# 15_2ND_AP1302_ISP.net
KiCad netlist of a schematic drawn in Altium Designer
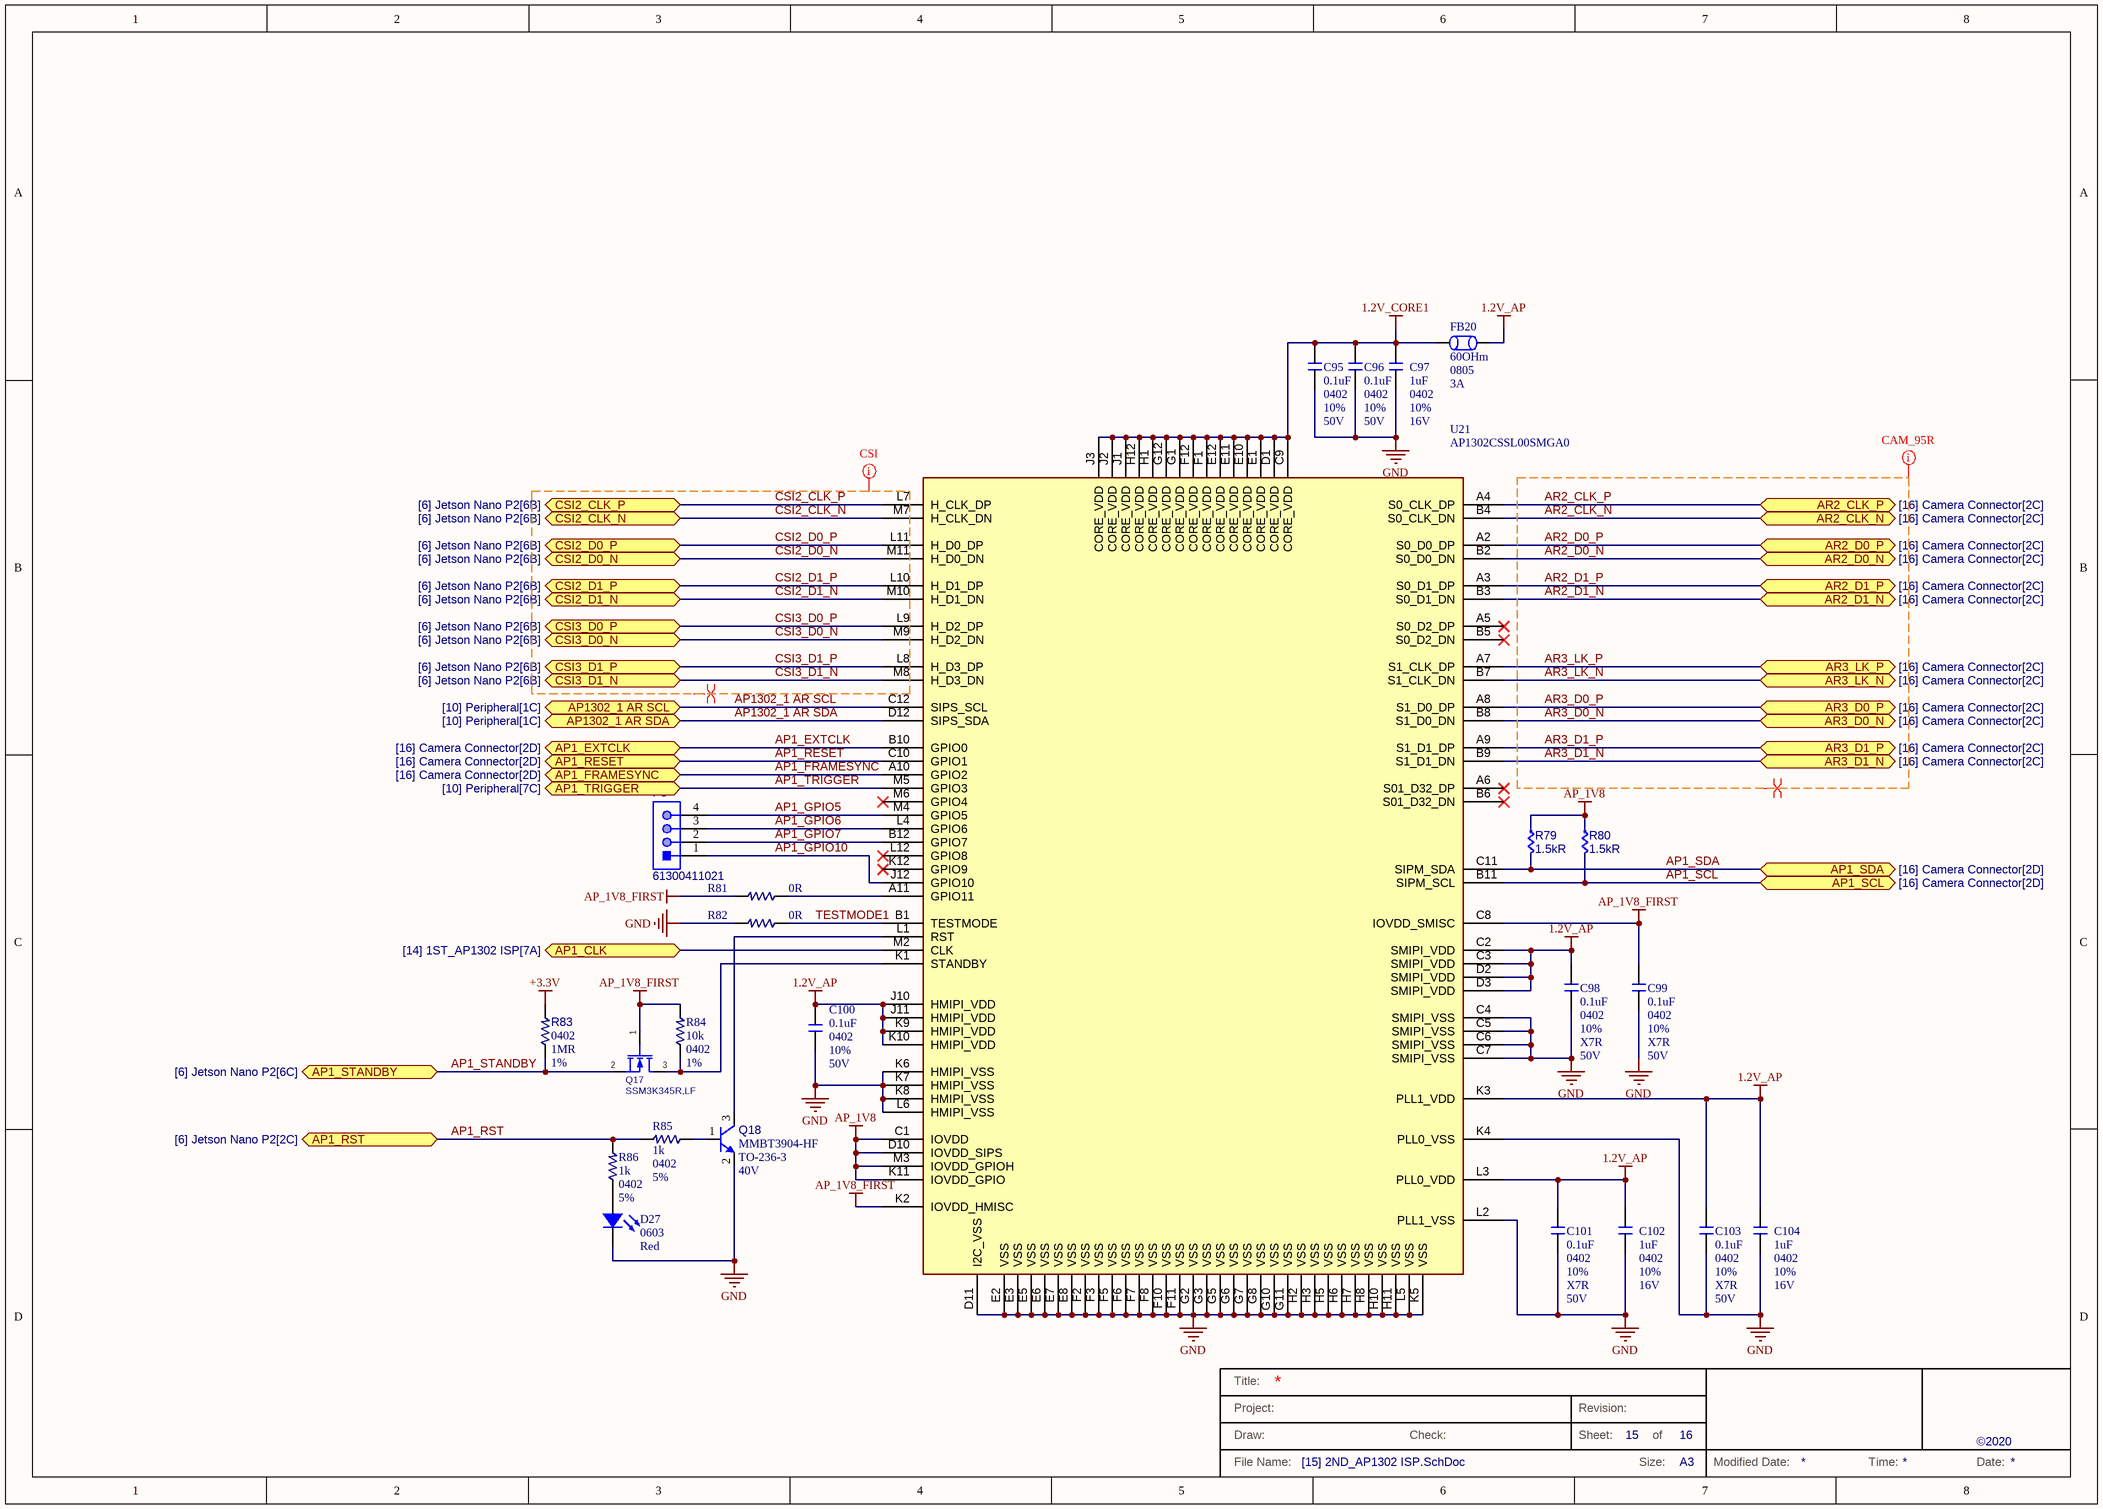
[diagram p0: [15] 2ND_AP1302 ISP.SchDoc]

(export (version "E")
  (design (tool "Eeschema 10.0.6"))
  (components
    (comp (ref "C95")
      (value "0.1uF")
      (footprint "C0402M")
      (description "CAP CER 0.1UF 50V X7R 0402")
      (fields
        (field (name "MANUFACTURER") "Murata")
        (field (name "MANUFACTURER PART NUMBER") "GRM155R71H104KE14D")
        (field (name "CASE/PACKAGE") "0402")
        (field (name "TOLERANCE") "10%")
        (field (name "VOLTAGE") "50V")
      )
      (libsource (lib "") (part "CAP_CER_1"))
    )
    (comp (ref "C96")
      (value "0.1uF")
      (footprint "C0402M")
      (description "CAP CER 0.1UF 50V X7R 0402")
      (fields
        (field (name "MANUFACTURER") "Murata")
        (field (name "MANUFACTURER PART NUMBER") "GRM155R71H104KE14D")
        (field (name "CASE/PACKAGE") "0402")
        (field (name "TOLERANCE") "10%")
        (field (name "VOLTAGE") "50V")
      )
      (libsource (lib "") (part "CAP_CER_1"))
    )
    (comp (ref "C97")
      (value "1uF")
      (footprint "C0402M")
      (fields
        (field (name "CASE CODE (IMPERIAL)") "0402")
        (field (name "TOLERANCE") "10%")
        (field (name "VOLTAGE") "16V")
      )
      (libsource (lib "CommonLib") (part "CAP_CER"))
    )
    (comp (ref "C98")
      (value "0.1uF")
      (footprint "C0402M")
      (description "CAP CER 0.1UF 50V X7R 0402")
      (fields
        (field (name "MANUFACTURER") "Murata")
        (field (name "MANUFACTURER PART NUMBER") "GRM155R71H104KE14D")
        (field (name "CASE/PACKAGE") "0402")
        (field (name "TOLERANCE") "10%")
        (field (name "DIELECTRIC") "X7R")
        (field (name "VOLTAGE") "50V")
      )
      (libsource (lib "") (part "CAP_CER_1"))
    )
    (comp (ref "C99")
      (value "0.1uF")
      (footprint "C0402M")
      (description "CAP CER 0.1UF 50V X7R 0402")
      (fields
        (field (name "MANUFACTURER") "Murata")
        (field (name "MANUFACTURER PART NUMBER") "GRM155R71H104KE14D")
        (field (name "CASE/PACKAGE") "0402")
        (field (name "TOLERANCE") "10%")
        (field (name "DIELECTRIC") "X7R")
        (field (name "VOLTAGE") "50V")
      )
      (libsource (lib "") (part "CAP_CER_1"))
    )
    (comp (ref "C100")
      (value "0.1uF")
      (footprint "C0402M")
      (description "CAP CER 0.1UF 50V X7R 0402")
      (fields
        (field (name "MANUFACTURER") "Murata")
        (field (name "MANUFACTURER PART NUMBER") "GRM155R71H104KE14D")
        (field (name "CASE/PACKAGE") "0402")
        (field (name "TOLERANCE") "10%")
        (field (name "VOLTAGE") "50V")
      )
      (libsource (lib "") (part "CAP_CER_1"))
    )
    (comp (ref "C101")
      (value "0.1uF")
      (footprint "C0402M")
      (description "CAP CER 0.1UF 50V X7R 0402")
      (fields
        (field (name "MANUFACTURER") "Murata")
        (field (name "MANUFACTURER PART NUMBER") "GRM155R71H104KE14D")
        (field (name "CASE/PACKAGE") "0402")
        (field (name "TOLERANCE") "10%")
        (field (name "DIELECTRIC") "X7R")
        (field (name "VOLTAGE") "50V")
      )
      (libsource (lib "") (part "CAP_CER_1"))
    )
    (comp (ref "C102")
      (value "1uF")
      (footprint "C0402M")
      (fields
        (field (name "CASE CODE (IMPERIAL)") "0402")
        (field (name "TOLERANCE") "10%")
        (field (name "VOLTAGE") "16V")
      )
      (libsource (lib "CommonLib") (part "CAP_CER"))
    )
    (comp (ref "C103")
      (value "0.1uF")
      (footprint "C0402M")
      (description "CAP CER 0.1UF 50V X7R 0402")
      (fields
        (field (name "MANUFACTURER") "Murata")
        (field (name "MANUFACTURER PART NUMBER") "GRM155R71H104KE14D")
        (field (name "CASE/PACKAGE") "0402")
        (field (name "TOLERANCE") "10%")
        (field (name "DIELECTRIC") "X7R")
        (field (name "VOLTAGE") "50V")
      )
      (libsource (lib "") (part "CAP_CER_1"))
    )
    (comp (ref "C104")
      (value "1uF")
      (footprint "C0402M")
      (fields
        (field (name "CASE CODE (IMPERIAL)") "0402")
        (field (name "TOLERANCE") "10%")
        (field (name "VOLTAGE") "16V")
      )
      (libsource (lib "CommonLib") (part "CAP_CER"))
    )
    (comp (ref "D27")
      (value "LTST-C190CKT")
      (footprint "LED-0603")
      (description "LED RED CLEAR CHIP SMD")
      (fields (field (name "CASE/PACKAGE") "0603") (field (name "COLOR") "Red"))
      (libsource (lib "CommonLib") (part "Led"))
    )
    (comp (ref "FB20")
      (value "60OHm")
      (footprint "R0805M")
      (fields
        (field (name "CASE CODE (IMPERIAL)") "0805")
        (field (name "TOLERANCE") "25%")
        (field (name "MAX DC CURRENT") "3A")
      )
      (libsource (lib "CommonLib") (part "FB"))
    )
    (comp (ref "P8")
      (value "61300411021")
      (footprint "61300411021")
      (description "CONN HEADER R/A 4POS 2.54MM")
      (fields (field (name "MANUFACTURER") "Würth Elektronik GmbH"))
      (libsource (lib "3DAS_4Camera") (part "WE-CN-1P-M-R4"))
    )
    (comp (ref "Q17")
      (value "SSM3K345R,LF")
      (footprint "SSM3K345R,LF-Footprint-1")
      (description "MOSFET N-CHANNEL 20V 4A SOT23F")
      (libsource (lib "Altium Central") (part "SSM3K345R,LF"))
    )
    (comp (ref "Q18")
      (value "NPN")
      (footprint "SOT55P160X90-3N")
      (description "TRANS NPN 40V 0.2A SOT523")
      (fields
        (field (name "MANUFACTURER PART NUMBER 1") "MMBT3904-HF")
        (field (name "CASE/PACKAGE") "TO-236-3")
        (field (name "COLLECTOR EMITTER BREAKDOWN VOLTAGE") "40V")
      )
      (libsource (lib "3DAS_4Camera") (part "NPN"))
    )
    (comp (ref "R79")
      (value "ERJ-2RKF1501X")
      (footprint "RES0402")
      (description "RES SMD 1.5K OHM 1% 1/10W 0402")
      (fields (field (name "RESISTANCE") "1.5kR") (field (name "TOLERANCE") "1%"))
      (libsource (lib "Altium Central") (part "=Resistance"))
    )
    (comp (ref "R80")
      (value "ERJ-2RKF1501X")
      (footprint "RES0402")
      (description "RES SMD 1.5K OHM 1% 1/10W 0402")
      (fields (field (name "RESISTANCE") "1.5kR") (field (name "TOLERANCE") "1%"))
      (libsource (lib "Altium Central") (part "=Resistance"))
    )
    (comp (ref "R81")
      (value "RC0402FR-070RL")
      (footprint "R0402M")
      (description "RC Series 0402 0.063 W 0 Ohm Jumper Surface Mount Thick Film Chip Resistor")
      (fields (field (name "RESISTANCE") "0R") (field (name "TOLERANCE") "1%"))
      (libsource (lib "CommonLib") (part "RES_SMD"))
    )
    (comp (ref "R82")
      (value "RC0402FR-070RL")
      (footprint "R0402M")
      (description "RC Series 0402 0.063 W 0 Ohm Jumper Surface Mount Thick Film Chip Resistor")
      (fields (field (name "RESISTANCE") "0R") (field (name "TOLERANCE") "1%"))
      (libsource (lib "CommonLib") (part "RES_SMD"))
    )
    (comp (ref "R83")
      (value "1M")
      (footprint "R0402M")
      (description "RES SMD 1M OHM 1% 1/16W 0402")
      (fields
        (field (name "MANUFACTURER") "Yageo")
        (field (name "MANUFACTURER PART NUMBER") "RC0402FR-071ML")
        (field (name "CASE CODE (IMPERIAL)") "0402")
        (field (name "RESISTANCE") "1MR")
        (field (name "TOLERANCE") "1%")
      )
      (libsource (lib "3DAS_4Camera") (part "RES_SMD_17"))
    )
    (comp (ref "R84")
      (value "10k")
      (footprint "R0402M")
      (description "RES SMD 10K OHM 1% 1/16W 0402")
      (fields
        (field (name "MANUFACTURER") "Yageo")
        (field (name "MANUFACTURER PART NUMBER") "RC0402FR-0710KL")
        (field (name "CASE CODE (IMPERIAL)") "0402")
        (field (name "TOLERANCE") "1%")
      )
      (libsource (lib "CommonLib") (part "RES_SMD"))
    )
    (comp (ref "R85")
      (value "1k")
      (footprint "R0402M")
      (description "RES SMD 1K OHM 5% 1/16W 0402")
      (fields
        (field (name "MANUFACTURER") "Yageo")
        (field (name "MANUFACTURER PART NUMBER") "RC0402JR-071KL")
        (field (name "CASE CODE (IMPERIAL)") "0402")
        (field (name "TOLERANCE") "5%")
      )
      (libsource (lib "CommonLib") (part "RES_SMD"))
    )
    (comp (ref "R86")
      (value "1k")
      (footprint "R0402M")
      (description "RES SMD 1K OHM 5% 1/16W 0402")
      (fields
        (field (name "MANUFACTURER") "Yageo")
        (field (name "MANUFACTURER PART NUMBER") "RC0402JR-071KL")
        (field (name "CASE CODE (IMPERIAL)") "0402")
        (field (name "TOLERANCE") "5%")
      )
      (libsource (lib "CommonLib") (part "RES_SMD"))
    )
    (comp (ref "U21")
      (value "AP1302CSSL00SMGA0")
      (footprint "AP1302CSSL00SMGA0")
      (description "IMAGE SENSOR 13 MP CO-PROCESSOR")
      (fields
        (field (name "MANUFACTURER") "ON Semiconductor")
        (field (name "MANUFACTURER PART NUMBER") "AP1302CSSL00SMGA0-DR")
      )
      (libsource (lib "3DAS_4Camera") (part "AP1302"))
    )
  )
  (nets
    (net (code "1") (name "+3.3V") (class "Default")
      (node (ref "R83") (pin "1") (pinfunction "1_1") (pintype "passive"))
    )
    (net (code "2") (name "/AP1_CLK") (class "Default")
      (node (ref "U21") (pin "M2") (pinfunction "CLK_M2") (pintype "passive"))
    )
    (net (code "3") (name "/AP1_EXTCLK") (class "Default")
      (node (ref "U21") (pin "B10") (pinfunction "GPIO0_B10") (pintype "passive"))
    )
    (net (code "4") (name "/AP1_FRAMESYNC") (class "Default")
      (node (ref "U21") (pin "A10") (pinfunction "GPIO2_A10") (pintype "passive"))
    )
    (net (code "5") (name "/AP1_GPIO5") (class "Default")
      (node (ref "P8") (pin "4") (pinfunction "4_4") (pintype "passive"))
      (node (ref "U21") (pin "M4") (pinfunction "GPIO5_M4") (pintype "passive"))
    )
    (net (code "6") (name "/AP1_GPIO6") (class "Default")
      (node (ref "P8") (pin "3") (pinfunction "3_3") (pintype "passive"))
      (node (ref "U21") (pin "L4") (pinfunction "GPIO6_L4") (pintype "passive"))
    )
    (net (code "7") (name "/AP1_GPIO7") (class "Default")
      (node (ref "P8") (pin "2") (pinfunction "2_2") (pintype "passive"))
      (node (ref "U21") (pin "B12") (pinfunction "GPIO7_B12") (pintype "passive"))
    )
    (net (code "8") (name "/AP1_GPIO10") (class "Default")
      (node (ref "P8") (pin "1") (pinfunction "1_1") (pintype "passive"))
      (node (ref "U21") (pin "J12") (pinfunction "GPIO10_J12") (pintype "passive"))
    )
    (net (code "9") (name "/AP1_RESET") (class "Default")
      (node (ref "U21") (pin "C10") (pinfunction "GPIO1_C10") (pintype "passive"))
    )
    (net (code "10") (name "/AP1_RST") (class "Default")
      (node (ref "R85") (pin "1") (pinfunction "1_1") (pintype "passive"))
      (node (ref "R86") (pin "1") (pinfunction "1_1") (pintype "passive"))
    )
    (net (code "11") (name "/AP1_SCL") (class "Default")
      (node (ref "R80") (pin "2") (pinfunction "2_2") (pintype "passive"))
      (node (ref "U21") (pin "B11") (pinfunction "SIPM_SCL_B11") (pintype "passive"))
    )
    (net (code "12") (name "/AP1_SDA") (class "Default")
      (node (ref "R79") (pin "2") (pinfunction "2_2") (pintype "passive"))
      (node (ref "U21") (pin "C11") (pinfunction "SIPM_SDA_C11") (pintype "passive"))
    )
    (net (code "13") (name "/AP1_STANDBY") (class "Default")
      (node (ref "Q17") (pin "2") (pinfunction "S_2") (pintype "passive"))
      (node (ref "R83") (pin "2") (pinfunction "2_2") (pintype "passive"))
    )
    (net (code "14") (name "/AP1_TRIGGER") (class "Default")
      (node (ref "U21") (pin "M5") (pinfunction "GPIO3_M5") (pintype "passive"))
    )
    (net (code "15") (name "/AP1302_1 AR SCL") (class "Default")
      (node (ref "U21") (pin "C12") (pinfunction "SIPS_SCL_C12") (pintype "passive"))
    )
    (net (code "16") (name "/AP1302_1 AR SDA") (class "Default")
      (node (ref "U21") (pin "D12") (pinfunction "SIPS_SDA_D12") (pintype "passive"))
    )
    (net (code "17") (name "/AR2_CLK_N") (class "Default")
      (node (ref "U21") (pin "B4") (pinfunction "S0_CLK_DN_B4") (pintype "passive"))
    )
    (net (code "18") (name "/AR2_CLK_P") (class "Default")
      (node (ref "U21") (pin "A4") (pinfunction "S0_CLK_DP_A4") (pintype "passive"))
    )
    (net (code "19") (name "/AR2_D0_N") (class "Default")
      (node (ref "U21") (pin "B2") (pinfunction "S0_D0_DN_B2") (pintype "passive"))
    )
    (net (code "20") (name "/AR2_D0_P") (class "Default")
      (node (ref "U21") (pin "A2") (pinfunction "S0_D0_DP_A2") (pintype "passive"))
    )
    (net (code "21") (name "/AR2_D1_N") (class "Default")
      (node (ref "U21") (pin "B3") (pinfunction "S0_D1_DN_B3") (pintype "passive"))
    )
    (net (code "22") (name "/AR2_D1_P") (class "Default")
      (node (ref "U21") (pin "A3") (pinfunction "S0_D1_DP_A3") (pintype "passive"))
    )
    (net (code "23") (name "/AR3_D0_N") (class "Default")
      (node (ref "U21") (pin "B8") (pinfunction "S1_D0_DN_B8") (pintype "passive"))
    )
    (net (code "24") (name "/AR3_D0_P") (class "Default")
      (node (ref "U21") (pin "A8") (pinfunction "S1_D0_DP_A8") (pintype "passive"))
    )
    (net (code "25") (name "/AR3_D1_N") (class "Default")
      (node (ref "U21") (pin "B9") (pinfunction "S1_D1_DN_B9") (pintype "passive"))
    )
    (net (code "26") (name "/AR3_D1_P") (class "Default")
      (node (ref "U21") (pin "A9") (pinfunction "S1_D1_DP_A9") (pintype "passive"))
    )
    (net (code "27") (name "/AR3_LK_N") (class "Default")
      (node (ref "U21") (pin "B7") (pinfunction "S1_CLK_DN_B7") (pintype "passive"))
    )
    (net (code "28") (name "/AR3_LK_P") (class "Default")
      (node (ref "U21") (pin "A7") (pinfunction "S1_CLK_DP_A7") (pintype "passive"))
    )
    (net (code "29") (name "/CSI2_CLK_N") (class "Default")
      (node (ref "U21") (pin "M7") (pinfunction "H_CLK_DN_M7") (pintype "passive"))
    )
    (net (code "30") (name "/CSI2_CLK_P") (class "Default")
      (node (ref "U21") (pin "L7") (pinfunction "H_CLK_DP_L7") (pintype "passive"))
    )
    (net (code "31") (name "/CSI2_D0_N") (class "Default")
      (node (ref "U21") (pin "M11") (pinfunction "H_D0_DN_M11") (pintype "passive"))
    )
    (net (code "32") (name "/CSI2_D0_P") (class "Default")
      (node (ref "U21") (pin "L11") (pinfunction "H_D0_DP_L11") (pintype "passive"))
    )
    (net (code "33") (name "/CSI2_D1_N") (class "Default")
      (node (ref "U21") (pin "M10") (pinfunction "H_D1_DN_M10") (pintype "passive"))
    )
    (net (code "34") (name "/CSI2_D1_P") (class "Default")
      (node (ref "U21") (pin "L10") (pinfunction "H_D1_DP_L10") (pintype "passive"))
    )
    (net (code "35") (name "/CSI3_D0_N") (class "Default")
      (node (ref "U21") (pin "M9") (pinfunction "H_D2_DN_M9") (pintype "passive"))
    )
    (net (code "36") (name "/CSI3_D0_P") (class "Default")
      (node (ref "U21") (pin "L9") (pinfunction "H_D2_DP_L9") (pintype "passive"))
    )
    (net (code "37") (name "/CSI3_D1_N") (class "Default")
      (node (ref "U21") (pin "M8") (pinfunction "H_D3_DN_M8") (pintype "passive"))
    )
    (net (code "38") (name "/CSI3_D1_P") (class "Default")
      (node (ref "U21") (pin "L8") (pinfunction "H_D3_DP_L8") (pintype "passive"))
    )
    (net (code "39") (name "/TESTMODE1") (class "Default")
      (node (ref "R82") (pin "2") (pinfunction "2_2") (pintype "passive"))
      (node (ref "U21") (pin "B1") (pinfunction "TESTMODE_B1") (pintype "passive"))
    )
    (net (code "40") (name "1.2V_AP") (class "Default")
      (node (ref "C100") (pin "1") (pinfunction "1_1") (pintype "passive"))
      (node (ref "C101") (pin "1") (pinfunction "1_1") (pintype "passive"))
      (node (ref "C102") (pin "1") (pinfunction "1_1") (pintype "passive"))
      (node (ref "C103") (pin "1") (pinfunction "1_1") (pintype "passive"))
      (node (ref "C104") (pin "1") (pinfunction "1_1") (pintype "passive"))
      (node (ref "C98") (pin "1") (pinfunction "1_1") (pintype "passive"))
      (node (ref "FB20") (pin "1") (pinfunction "1_1") (pintype "passive"))
      (node (ref "U21") (pin "C2") (pinfunction "SMIPI_VDD_C2") (pintype "passive"))
      (node (ref "U21") (pin "C3") (pinfunction "SMIPI_VDD_C3") (pintype "passive"))
      (node (ref "U21") (pin "D2") (pinfunction "SMIPI_VDD_D2") (pintype "passive"))
      (node (ref "U21") (pin "D3") (pinfunction "SMIPI_VDD_D3") (pintype "passive"))
      (node (ref "U21") (pin "J10") (pinfunction "HMIPI_VDD_J10") (pintype "passive"))
      (node (ref "U21") (pin "J11") (pinfunction "HMIPI_VDD_J11") (pintype "passive"))
      (node (ref "U21") (pin "K10") (pinfunction "HMIPI_VDD_K10") (pintype "passive"))
      (node (ref "U21") (pin "K3") (pinfunction "PLL1_VDD_K3") (pintype "passive"))
      (node (ref "U21") (pin "K9") (pinfunction "HMIPI_VDD_K9") (pintype "passive"))
      (node (ref "U21") (pin "L3") (pinfunction "PLL0_VDD_L3") (pintype "passive"))
    )
    (net (code "41") (name "1.2V_CORE1") (class "Default")
      (node (ref "C95") (pin "1") (pinfunction "1_1") (pintype "passive"))
      (node (ref "C96") (pin "1") (pinfunction "1_1") (pintype "passive"))
      (node (ref "C97") (pin "1") (pinfunction "1_1") (pintype "passive"))
      (node (ref "FB20") (pin "2") (pinfunction "2_2") (pintype "passive"))
      (node (ref "U21") (pin "C9") (pinfunction "CORE_VDD_C9") (pintype "passive"))
      (node (ref "U21") (pin "D1") (pinfunction "CORE_VDD_D1") (pintype "passive"))
      (node (ref "U21") (pin "E1") (pinfunction "CORE_VDD_E1") (pintype "passive"))
      (node (ref "U21") (pin "E10") (pinfunction "CORE_VDD_E10") (pintype "passive"))
      (node (ref "U21") (pin "E11") (pinfunction "CORE_VDD_E11") (pintype "passive"))
      (node (ref "U21") (pin "E12") (pinfunction "CORE_VDD_E12") (pintype "passive"))
      (node (ref "U21") (pin "F1") (pinfunction "CORE_VDD_F1") (pintype "passive"))
      (node (ref "U21") (pin "F12") (pinfunction "CORE_VDD_F12") (pintype "passive"))
      (node (ref "U21") (pin "G1") (pinfunction "CORE_VDD_G1") (pintype "passive"))
      (node (ref "U21") (pin "G12") (pinfunction "CORE_VDD_G12") (pintype "passive"))
      (node (ref "U21") (pin "H1") (pinfunction "CORE_VDD_H1") (pintype "passive"))
      (node (ref "U21") (pin "H12") (pinfunction "CORE_VDD_H12") (pintype "passive"))
      (node (ref "U21") (pin "J1") (pinfunction "CORE_VDD_J1") (pintype "passive"))
      (node (ref "U21") (pin "J2") (pinfunction "CORE_VDD_J2") (pintype "passive"))
      (node (ref "U21") (pin "J3") (pinfunction "CORE_VDD_J3") (pintype "passive"))
    )
    (net (code "42") (name "AP_1V8") (class "Default")
      (node (ref "R79") (pin "1") (pinfunction "1_1") (pintype "passive"))
      (node (ref "R80") (pin "1") (pinfunction "1_1") (pintype "passive"))
      (node (ref "U21") (pin "C1") (pinfunction "IOVDD_C1") (pintype "passive"))
      (node (ref "U21") (pin "D10") (pinfunction "IOVDD_SIPS_D10") (pintype "passive"))
      (node (ref "U21") (pin "K11") (pinfunction "IOVDD_GPIO_K11") (pintype "passive"))
      (node (ref "U21") (pin "M3") (pinfunction "IOVDD_GPIOH_M3") (pintype "passive"))
    )
    (net (code "43") (name "AP_1V8_FIRST") (class "Default")
      (node (ref "C99") (pin "1") (pinfunction "1_1") (pintype "passive"))
      (node (ref "Q17") (pin "1") (pinfunction "G_1") (pintype "passive"))
      (node (ref "R81") (pin "1") (pinfunction "1_1") (pintype "passive"))
      (node (ref "R84") (pin "1") (pinfunction "1_1") (pintype "passive"))
      (node (ref "U21") (pin "C8") (pinfunction "IOVDD_SMISC_C8") (pintype "passive"))
      (node (ref "U21") (pin "K2") (pinfunction "IOVDD_HMISC_K2") (pintype "passive"))
    )
    (net (code "44") (name "GND") (class "Default")
      (node (ref "C100") (pin "2") (pinfunction "2_2") (pintype "passive"))
      (node (ref "C101") (pin "2") (pinfunction "2_2") (pintype "passive"))
      (node (ref "C102") (pin "2") (pinfunction "2_2") (pintype "passive"))
      (node (ref "C103") (pin "2") (pinfunction "2_2") (pintype "passive"))
      (node (ref "C104") (pin "2") (pinfunction "2_2") (pintype "passive"))
      (node (ref "C95") (pin "2") (pinfunction "2_2") (pintype "passive"))
      (node (ref "C96") (pin "2") (pinfunction "2_2") (pintype "passive"))
      (node (ref "C97") (pin "2") (pinfunction "2_2") (pintype "passive"))
      (node (ref "C98") (pin "2") (pinfunction "2_2") (pintype "passive"))
      (node (ref "C99") (pin "2") (pinfunction "2_2") (pintype "passive"))
      (node (ref "D27") (pin "2") (pinfunction "K_2") (pintype "passive"))
      (node (ref "Q18") (pin "2") (pinfunction "E_2") (pintype "passive"))
      (node (ref "R82") (pin "1") (pinfunction "1_1") (pintype "passive"))
      (node (ref "U21") (pin "C4") (pinfunction "SMIPI_VSS_C4") (pintype "passive"))
      (node (ref "U21") (pin "C5") (pinfunction "SMIPI_VSS_C5") (pintype "passive"))
      (node (ref "U21") (pin "C6") (pinfunction "SMIPI_VSS_C6") (pintype "passive"))
      (node (ref "U21") (pin "C7") (pinfunction "SMIPI_VSS_C7") (pintype "passive"))
      (node (ref "U21") (pin "D11") (pinfunction "I2C_VSS_D11") (pintype "passive"))
      (node (ref "U21") (pin "E2") (pinfunction "VSS_E2") (pintype "passive"))
      (node (ref "U21") (pin "E3") (pinfunction "VSS_E3") (pintype "passive"))
      (node (ref "U21") (pin "E5") (pinfunction "VSS_E5") (pintype "passive"))
      (node (ref "U21") (pin "E6") (pinfunction "VSS_E6") (pintype "passive"))
      (node (ref "U21") (pin "E7") (pinfunction "VSS_E7") (pintype "passive"))
      (node (ref "U21") (pin "E8") (pinfunction "VSS_E8") (pintype "passive"))
      (node (ref "U21") (pin "F10") (pinfunction "VSS_F10") (pintype "passive"))
      (node (ref "U21") (pin "F11") (pinfunction "VSS_F11") (pintype "passive"))
      (node (ref "U21") (pin "F2") (pinfunction "VSS_F2") (pintype "passive"))
      (node (ref "U21") (pin "F3") (pinfunction "VSS_F3") (pintype "passive"))
      (node (ref "U21") (pin "F5") (pinfunction "VSS_F5") (pintype "passive"))
      (node (ref "U21") (pin "F6") (pinfunction "VSS_F6") (pintype "passive"))
      (node (ref "U21") (pin "F7") (pinfunction "VSS_F7") (pintype "passive"))
      (node (ref "U21") (pin "F8") (pinfunction "VSS_F8") (pintype "passive"))
      (node (ref "U21") (pin "G10") (pinfunction "VSS_G10") (pintype "passive"))
      (node (ref "U21") (pin "G11") (pinfunction "VSS_G11") (pintype "passive"))
      (node (ref "U21") (pin "G2") (pinfunction "VSS_G2") (pintype "passive"))
      (node (ref "U21") (pin "G3") (pinfunction "VSS_G3") (pintype "passive"))
      (node (ref "U21") (pin "G5") (pinfunction "VSS_G5") (pintype "passive"))
      (node (ref "U21") (pin "G6") (pinfunction "VSS_G6") (pintype "passive"))
      (node (ref "U21") (pin "G7") (pinfunction "VSS_G7") (pintype "passive"))
      (node (ref "U21") (pin "G8") (pinfunction "VSS_G8") (pintype "passive"))
      (node (ref "U21") (pin "H10") (pinfunction "VSS_H10") (pintype "passive"))
      (node (ref "U21") (pin "H11") (pinfunction "VSS_H11") (pintype "passive"))
      (node (ref "U21") (pin "H2") (pinfunction "VSS_H2") (pintype "passive"))
      (node (ref "U21") (pin "H3") (pinfunction "VSS_H3") (pintype "passive"))
      (node (ref "U21") (pin "H5") (pinfunction "VSS_H5") (pintype "passive"))
      (node (ref "U21") (pin "H6") (pinfunction "VSS_H6") (pintype "passive"))
      (node (ref "U21") (pin "H7") (pinfunction "VSS_H7") (pintype "passive"))
      (node (ref "U21") (pin "H8") (pinfunction "VSS_H8") (pintype "passive"))
      (node (ref "U21") (pin "K4") (pinfunction "PLL0_VSS_K4") (pintype "passive"))
      (node (ref "U21") (pin "K5") (pinfunction "VSS_K5") (pintype "passive"))
      (node (ref "U21") (pin "K6") (pinfunction "HMIPI_VSS_K6") (pintype "passive"))
      (node (ref "U21") (pin "K7") (pinfunction "HMIPI_VSS_K7") (pintype "passive"))
      (node (ref "U21") (pin "K8") (pinfunction "HMIPI_VSS_K8") (pintype "passive"))
      (node (ref "U21") (pin "L2") (pinfunction "PLL1_VSS_L2") (pintype "passive"))
      (node (ref "U21") (pin "L5") (pinfunction "VSS_L5") (pintype "passive"))
      (node (ref "U21") (pin "L6") (pinfunction "HMIPI_VSS_L6") (pintype "passive"))
    )
    (net (code "45") (name "Net-(D27-A)") (class "Default")
      (node (ref "D27") (pin "1") (pinfunction "A_1") (pintype "passive"))
      (node (ref "R86") (pin "2") (pinfunction "2_2") (pintype "passive"))
    )
    (net (code "46") (name "Net-(Q17-D)") (class "Default")
      (node (ref "Q17") (pin "3") (pinfunction "D_3") (pintype "passive"))
      (node (ref "R84") (pin "2") (pinfunction "2_2") (pintype "passive"))
      (node (ref "U21") (pin "K1") (pinfunction "STANDBY_K1") (pintype "passive"))
    )
    (net (code "47") (name "Net-(Q18-B)") (class "Default")
      (node (ref "Q18") (pin "1") (pinfunction "B_1") (pintype "passive"))
      (node (ref "R85") (pin "2") (pinfunction "2_2") (pintype "passive"))
    )
    (net (code "48") (name "Net-(Q18-C)") (class "Default")
      (node (ref "Q18") (pin "3") (pinfunction "C_3") (pintype "passive"))
      (node (ref "U21") (pin "L1") (pinfunction "RST_L1") (pintype "passive"))
    )
    (net (code "49") (name "Net-(U21-GPIO11)") (class "Default")
      (node (ref "R81") (pin "2") (pinfunction "2_2") (pintype "passive"))
      (node (ref "U21") (pin "A11") (pinfunction "GPIO11_A11") (pintype "passive"))
    )
    (net (code "50") (name "unconnected-(U21-GPIO4-PadM6)") (class "Default")
      (node (ref "U21") (pin "M6") (pinfunction "GPIO4_M6") (pintype "passive+no_connect"))
    )
    (net (code "51") (name "unconnected-(U21-GPIO8-PadL12)") (class "Default")
      (node (ref "U21") (pin "L12") (pinfunction "GPIO8_L12") (pintype "passive+no_connect"))
    )
    (net (code "52") (name "unconnected-(U21-GPIO9-PadK12)") (class "Default")
      (node (ref "U21") (pin "K12") (pinfunction "GPIO9_K12") (pintype "passive+no_connect"))
    )
    (net (code "53") (name "unconnected-(U21-S0_D2_DN-PadB5)") (class "Default")
      (node (ref "U21") (pin "B5") (pinfunction "S0_D2_DN_B5") (pintype "passive+no_connect"))
    )
    (net (code "54") (name "unconnected-(U21-S0_D2_DP-PadA5)") (class "Default")
      (node (ref "U21") (pin "A5") (pinfunction "S0_D2_DP_A5") (pintype "passive+no_connect"))
    )
    (net (code "55") (name "unconnected-(U21-S01_D32_DN-PadB6)") (class "Default")
      (node (ref "U21") (pin "B6") (pinfunction "S01_D32_DN_B6") (pintype "passive+no_connect"))
    )
    (net (code "56") (name "unconnected-(U21-S01_D32_DP-PadA6)") (class "Default")
      (node (ref "U21") (pin "A6") (pinfunction "S01_D32_DP_A6") (pintype "passive+no_connect"))
    )
  )
)
